# SD_NAND.net
KiCad netlist of a schematic drawn in Altium Designer
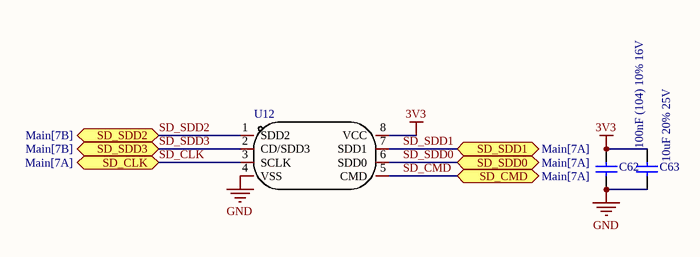
[diagram p0: SD NAND.SchDoc]

(export (version "E")
  (design (tool "Eeschema 10.0.6"))
  (components
    (comp (ref "C62")
      (value "100nF (104) 10% 16V")
      (footprint "0402_C")
      (description "贴片电容")
      (libsource (lib "Cap") (part "0402 100nF (104) 10% 16V"))
    )
    (comp (ref "C63")
      (value "10uF 20% 25V")
      (footprint "0402_C")
      (description "贴片电容")
      (libsource (lib "Cap") (part "0603 10uF (106) 10% 10V"))
    )
    (comp (ref "U12")
      (value "CSNP1GCR01-BOW")
      (footprint "LGA-8_L6.0-W8.0-P1.27-TL")
      (fields (field (name "MANUFACTURER") "CS(创世)"))
      (libsource (lib "altium-import") (part "root_0_CSNP1GCR01-BOW_"))
    )
  )
  (nets
    (net (code "1") (name "/SD_CLK") (class "Default")
      (node (ref "U12") (pin "3") (pinfunction "SCLK_3") (pintype "passive"))
    )
    (net (code "2") (name "/SD_CMD") (class "Default")
      (node (ref "U12") (pin "5") (pinfunction "CMD_5") (pintype "passive"))
    )
    (net (code "3") (name "/SD_SDD0") (class "Default")
      (node (ref "U12") (pin "6") (pinfunction "SDD0_6") (pintype "passive"))
    )
    (net (code "4") (name "/SD_SDD1") (class "Default")
      (node (ref "U12") (pin "7") (pinfunction "SDD1_7") (pintype "passive"))
    )
    (net (code "5") (name "/SD_SDD2") (class "Default")
      (node (ref "U12") (pin "1") (pinfunction "SDD2_1") (pintype "passive"))
    )
    (net (code "6") (name "/SD_SDD3") (class "Default")
      (node (ref "U12") (pin "2") (pinfunction "CD/SDD3_2") (pintype "passive"))
    )
    (net (code "7") (name "3V3") (class "Default")
      (node (ref "C62") (pin "1") (pinfunction "1_1") (pintype "passive"))
      (node (ref "C63") (pin "2") (pinfunction "2_2") (pintype "passive"))
      (node (ref "U12") (pin "8") (pinfunction "VCC_8") (pintype "passive"))
    )
    (net (code "8") (name "GND") (class "Default")
      (node (ref "C62") (pin "2") (pinfunction "2_2") (pintype "passive"))
      (node (ref "C63") (pin "1") (pinfunction "1_1") (pintype "passive"))
      (node (ref "U12") (pin "4") (pinfunction "VSS_4") (pintype "passive"))
    )
  )
)
